# PiWing.net
KiCad netlist of a schematic drawn in EAGLE
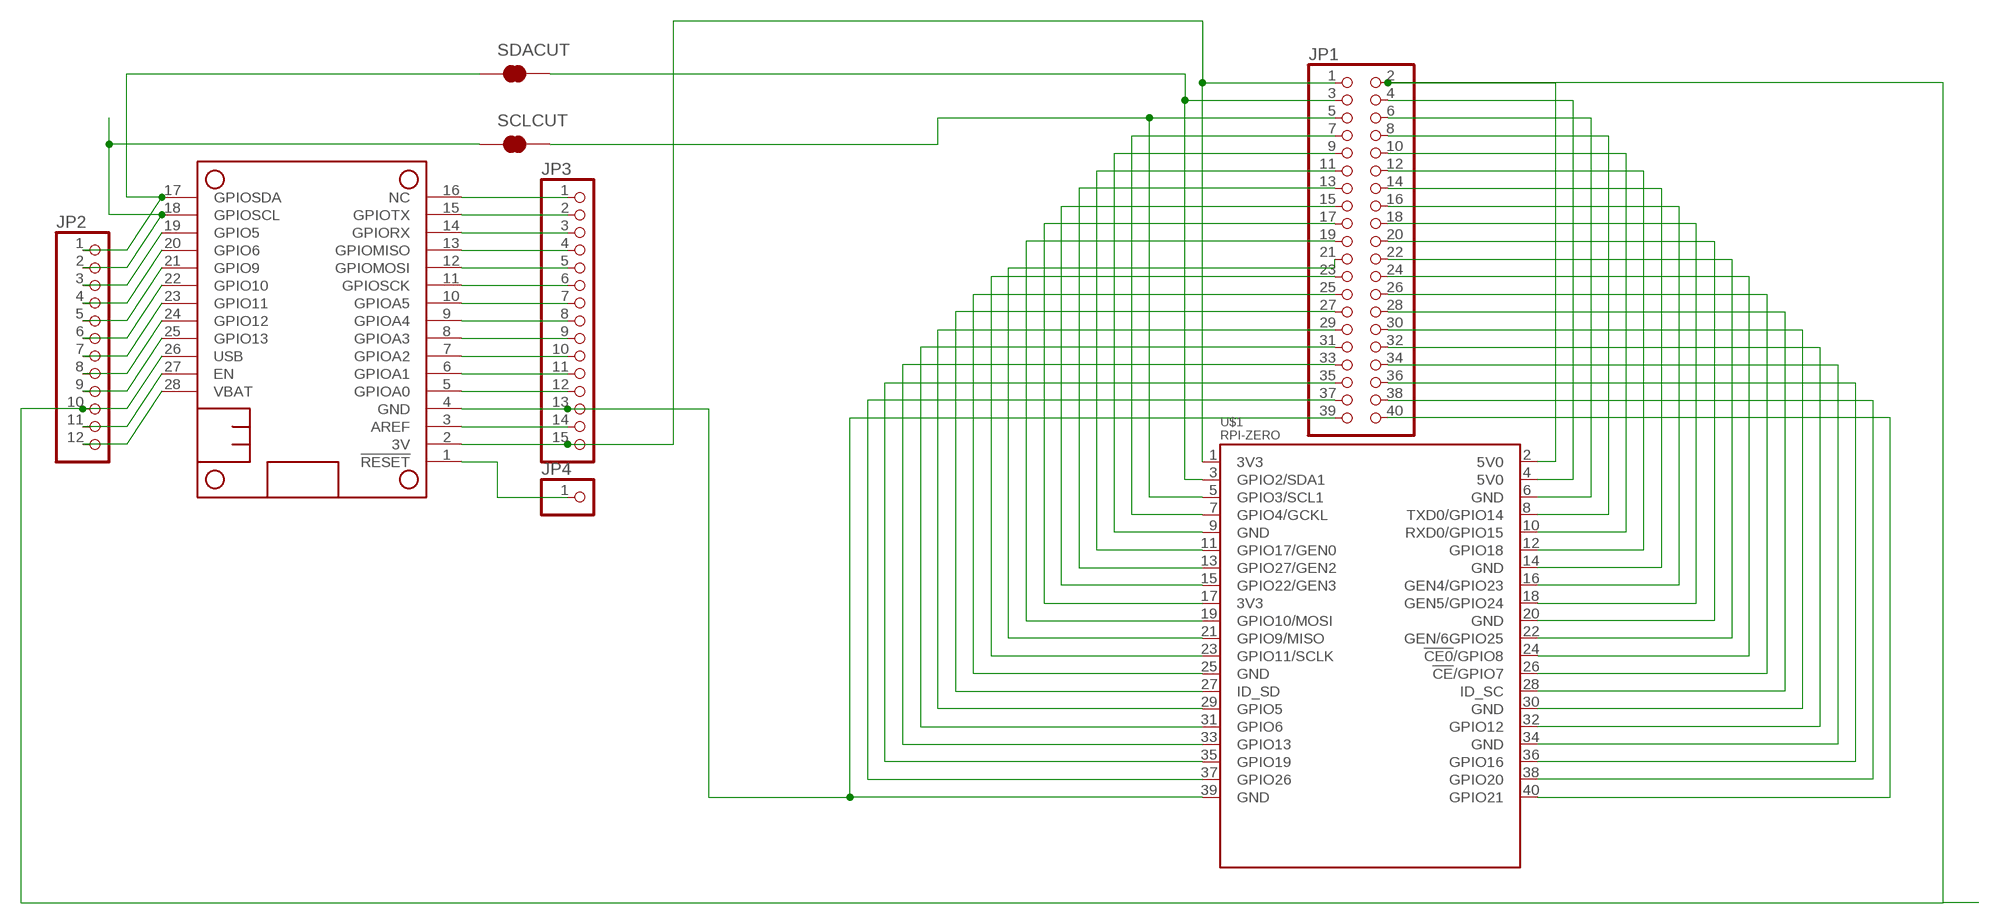
[diagram p0: schematic, sheet 1]

(export (version "E")
  (design (tool "Eeschema 10.0.6"))
  (components
    (comp (ref "JP1")
      (value "PINHD-2X20-BIG")
      (footprint "eagle-import:2X20-BIG")
      (libsource (lib "eagle-import") (part "PINHD-2X20-BIG"))
    )
    (comp (ref "JP2")
      (value "PINHD-1X12-CB")
      (footprint "eagle-import:1X12-CB")
      (libsource (lib "eagle-import") (part "PINHD-1X12-CB"))
    )
    (comp (ref "JP3")
      (value "PINHD-1X15-CB")
      (footprint "eagle-import:1X15-CB")
      (libsource (lib "eagle-import") (part "PINHD-1X15-CB"))
    )
    (comp (ref "JP4")
      (value "PINHD-1X1CB")
      (footprint "eagle-import:1X01-CLEANBIG")
      (libsource (lib "eagle-import") (part "PINHD-1X1CB"))
    )
    (comp (ref "MS1")
      (value "FEATHERWING_NODIM")
      (footprint "eagle-import:FEATHERWING_DIM")
      (libsource (lib "eagle-import") (part "FEATHERWING_NODIM"))
    )
    (comp (ref "SCLCUT")
      (value "JUMPER-SMT_2_NC_TRACE_SILK")
      (footprint "eagle-import:SMT-JUMPER_2_NC_TRACE_SILK")
      (libsource (lib "eagle-import") (part "JUMPER-SMT_2_NC_TRACE_SILK"))
    )
    (comp (ref "SDACUT")
      (value "JUMPER-SMT_2_NC_TRACE_SILK")
      (footprint "eagle-import:SMT-JUMPER_2_NC_TRACE_SILK")
      (libsource (lib "eagle-import") (part "JUMPER-SMT_2_NC_TRACE_SILK"))
    )
    (comp (ref "U$1")
      (value "RPI-ZERO")
      (footprint "eagle-import:RASPBERRYPI_BASTELSTUBE_V13_RASPI_BOARD_B+_FULL")
      (libsource (lib "eagle-import") (part "RPI-ZERO"))
    )
  )
  (nets
    (net (code "1") (name "Net-(JP1-Pad4)") (class "Default")
      (node (ref "JP1") (pin "4") (pinfunction "4_4") (pintype "passive"))
      (node (ref "U$1") (pin "4") (pinfunction "5V0_4") (pintype "power_in"))
    )
    (net (code "2") (name "Net-(JP1-Pad6)") (class "Default")
      (node (ref "JP1") (pin "6") (pinfunction "6_6") (pintype "passive"))
      (node (ref "U$1") (pin "6") (pinfunction "GND_6") (pintype "power_in"))
    )
    (net (code "3") (name "Net-(JP1-Pad9)") (class "Default")
      (node (ref "JP1") (pin "9") (pinfunction "9_9") (pintype "passive"))
      (node (ref "U$1") (pin "9") (pinfunction "GND_9") (pintype "power_in"))
    )
    (net (code "4") (name "Net-(JP1-Pad14)") (class "Default")
      (node (ref "JP1") (pin "14") (pinfunction "14_14") (pintype "passive"))
      (node (ref "U$1") (pin "14") (pinfunction "GND_14") (pintype "power_in"))
    )
    (net (code "5") (name "Net-(JP1-Pad17)") (class "Default")
      (node (ref "JP1") (pin "17") (pinfunction "17_17") (pintype "passive"))
      (node (ref "U$1") (pin "17") (pinfunction "3V3_17") (pintype "power_in"))
    )
    (net (code "6") (name "Net-(JP1-Pad20)") (class "Default")
      (node (ref "JP1") (pin "20") (pinfunction "20_20") (pintype "passive"))
      (node (ref "U$1") (pin "20") (pinfunction "GND_20") (pintype "power_in"))
    )
    (net (code "7") (name "Net-(JP1-Pad25)") (class "Default")
      (node (ref "JP1") (pin "25") (pinfunction "25_25") (pintype "passive"))
      (node (ref "U$1") (pin "25") (pinfunction "GND_25") (pintype "power_in"))
    )
    (net (code "8") (name "Net-(JP1-Pad30)") (class "Default")
      (node (ref "JP1") (pin "30") (pinfunction "30_30") (pintype "passive"))
      (node (ref "U$1") (pin "30") (pinfunction "GND_30") (pintype "power_in"))
    )
    (net (code "9") (name "Net-(JP1-Pad34)") (class "Default")
      (node (ref "JP1") (pin "34") (pinfunction "34_34") (pintype "passive"))
      (node (ref "U$1") (pin "34") (pinfunction "GND_34") (pintype "power_in"))
    )
    (net (code "10") (name "Net-(MS1-3V)") (class "Default")
      (node (ref "JP1") (pin "1") (pinfunction "1_1") (pintype "passive"))
      (node (ref "JP3") (pin "15") (pinfunction "15_15") (pintype "passive"))
      (node (ref "MS1") (pin "2") (pinfunction "3V_2") (pintype "power_in"))
      (node (ref "U$1") (pin "1") (pinfunction "3V3_1") (pintype "power_in"))
    )
    (net (code "11") (name "Net-(MS1-AREF)") (class "Default")
      (node (ref "JP3") (pin "14") (pinfunction "14_14") (pintype "passive"))
      (node (ref "MS1") (pin "3") (pinfunction "AREF_3") (pintype "passive"))
    )
    (net (code "12") (name "Net-(MS1-EN)") (class "Default")
      (node (ref "JP2") (pin "11") (pinfunction "11_11") (pintype "passive"))
      (node (ref "MS1") (pin "27") (pinfunction "EN_27") (pintype "passive"))
    )
    (net (code "13") (name "Net-(MS1-GND)") (class "Default")
      (node (ref "JP1") (pin "39") (pinfunction "39_39") (pintype "passive"))
      (node (ref "JP3") (pin "13") (pinfunction "13_13") (pintype "passive"))
      (node (ref "MS1") (pin "4") (pinfunction "GND_4") (pintype "power_in"))
      (node (ref "U$1") (pin "39") (pinfunction "GND_39") (pintype "power_in"))
    )
    (net (code "14") (name "Net-(MS1-GPIO5)") (class "Default")
      (node (ref "JP2") (pin "3") (pinfunction "3_3") (pintype "passive"))
      (node (ref "MS1") (pin "19") (pinfunction "GPIO5_19") (pintype "bidirectional"))
    )
    (net (code "15") (name "Net-(MS1-GPIO6)") (class "Default")
      (node (ref "JP2") (pin "4") (pinfunction "4_4") (pintype "passive"))
      (node (ref "MS1") (pin "20") (pinfunction "GPIO6_20") (pintype "bidirectional"))
    )
    (net (code "16") (name "Net-(MS1-GPIO9)") (class "Default")
      (node (ref "JP2") (pin "5") (pinfunction "5_5") (pintype "passive"))
      (node (ref "MS1") (pin "21") (pinfunction "GPIO9_21") (pintype "bidirectional"))
    )
    (net (code "17") (name "Net-(MS1-GPIO10)") (class "Default")
      (node (ref "JP2") (pin "6") (pinfunction "6_6") (pintype "passive"))
      (node (ref "MS1") (pin "22") (pinfunction "GPIO10_22") (pintype "bidirectional"))
    )
    (net (code "18") (name "Net-(MS1-GPIO11)") (class "Default")
      (node (ref "JP2") (pin "7") (pinfunction "7_7") (pintype "passive"))
      (node (ref "MS1") (pin "23") (pinfunction "GPIO11_23") (pintype "bidirectional"))
    )
    (net (code "19") (name "Net-(MS1-GPIO12)") (class "Default")
      (node (ref "JP2") (pin "8") (pinfunction "8_8") (pintype "passive"))
      (node (ref "MS1") (pin "24") (pinfunction "GPIO12_24") (pintype "bidirectional"))
    )
    (net (code "20") (name "Net-(MS1-GPIO13)") (class "Default")
      (node (ref "JP2") (pin "9") (pinfunction "9_9") (pintype "passive"))
      (node (ref "MS1") (pin "25") (pinfunction "GPIO13_25") (pintype "bidirectional"))
    )
    (net (code "21") (name "Net-(MS1-GPIOA0)") (class "Default")
      (node (ref "JP3") (pin "12") (pinfunction "12_12") (pintype "passive"))
      (node (ref "MS1") (pin "5") (pinfunction "GPIOA0_5") (pintype "bidirectional"))
    )
    (net (code "22") (name "Net-(MS1-GPIOA1)") (class "Default")
      (node (ref "JP3") (pin "11") (pinfunction "11_11") (pintype "passive"))
      (node (ref "MS1") (pin "6") (pinfunction "GPIOA1_6") (pintype "bidirectional"))
    )
    (net (code "23") (name "Net-(MS1-GPIOA2)") (class "Default")
      (node (ref "JP3") (pin "10") (pinfunction "10_10") (pintype "passive"))
      (node (ref "MS1") (pin "7") (pinfunction "GPIOA2_7") (pintype "bidirectional"))
    )
    (net (code "24") (name "Net-(MS1-GPIOA3)") (class "Default")
      (node (ref "JP3") (pin "9") (pinfunction "9_9") (pintype "passive"))
      (node (ref "MS1") (pin "8") (pinfunction "GPIOA3_8") (pintype "bidirectional"))
    )
    (net (code "25") (name "Net-(MS1-GPIOA4)") (class "Default")
      (node (ref "JP3") (pin "8") (pinfunction "8_8") (pintype "passive"))
      (node (ref "MS1") (pin "9") (pinfunction "GPIOA4_9") (pintype "bidirectional"))
    )
    (net (code "26") (name "Net-(MS1-GPIOA5)") (class "Default")
      (node (ref "JP3") (pin "7") (pinfunction "7_7") (pintype "passive"))
      (node (ref "MS1") (pin "10") (pinfunction "GPIOA5_10") (pintype "bidirectional"))
    )
    (net (code "27") (name "Net-(MS1-GPIOMISO)") (class "Default")
      (node (ref "JP3") (pin "4") (pinfunction "4_4") (pintype "passive"))
      (node (ref "MS1") (pin "13") (pinfunction "GPIOMISO_13") (pintype "bidirectional"))
    )
    (net (code "28") (name "Net-(MS1-GPIOMOSI)") (class "Default")
      (node (ref "JP3") (pin "5") (pinfunction "5_5") (pintype "passive"))
      (node (ref "MS1") (pin "12") (pinfunction "GPIOMOSI_12") (pintype "bidirectional"))
    )
    (net (code "29") (name "Net-(MS1-GPIORX)") (class "Default")
      (node (ref "JP3") (pin "3") (pinfunction "3_3") (pintype "passive"))
      (node (ref "MS1") (pin "14") (pinfunction "GPIORX_14") (pintype "bidirectional"))
    )
    (net (code "30") (name "Net-(MS1-GPIOSCK)") (class "Default")
      (node (ref "JP3") (pin "6") (pinfunction "6_6") (pintype "passive"))
      (node (ref "MS1") (pin "11") (pinfunction "GPIOSCK_11") (pintype "bidirectional"))
    )
    (net (code "31") (name "Net-(MS1-GPIOSCL)") (class "Default")
      (node (ref "JP2") (pin "2") (pinfunction "2_2") (pintype "passive"))
      (node (ref "MS1") (pin "18") (pinfunction "GPIOSCL_18") (pintype "bidirectional"))
      (node (ref "SCLCUT") (pin "1") (pinfunction "1_1") (pintype "passive"))
    )
    (net (code "32") (name "Net-(MS1-GPIOSDA)") (class "Default")
      (node (ref "JP2") (pin "1") (pinfunction "1_1") (pintype "passive"))
      (node (ref "MS1") (pin "17") (pinfunction "GPIOSDA_17") (pintype "bidirectional"))
      (node (ref "SDACUT") (pin "1") (pinfunction "1_1") (pintype "passive"))
    )
    (net (code "33") (name "Net-(MS1-GPIOTX)") (class "Default")
      (node (ref "JP3") (pin "2") (pinfunction "2_2") (pintype "passive"))
      (node (ref "MS1") (pin "15") (pinfunction "GPIOTX_15") (pintype "bidirectional"))
    )
    (net (code "34") (name "Net-(MS1-NC)") (class "Default")
      (node (ref "JP3") (pin "1") (pinfunction "1_1") (pintype "passive"))
      (node (ref "MS1") (pin "16") (pinfunction "NC_16") (pintype "passive"))
    )
    (net (code "35") (name "Net-(MS1-USB)") (class "Default")
      (node (ref "JP1") (pin "2") (pinfunction "2_2") (pintype "passive"))
      (node (ref "JP2") (pin "10") (pinfunction "10_10") (pintype "passive"))
      (node (ref "MS1") (pin "26") (pinfunction "USB_26") (pintype "power_in"))
      (node (ref "U$1") (pin "2") (pinfunction "5V0_2") (pintype "power_in"))
    )
    (net (code "36") (name "Net-(MS1-VBAT)") (class "Default")
      (node (ref "JP2") (pin "12") (pinfunction "12_12") (pintype "passive"))
      (node (ref "MS1") (pin "28") (pinfunction "VBAT_28") (pintype "power_in"))
    )
    (net (code "37") (name "Net-(MS1-~{RESET})") (class "Default")
      (node (ref "JP4") (pin "1") (pinfunction "1_1") (pintype "passive"))
      (node (ref "MS1") (pin "1") (pinfunction "~{RESET}_1") (pintype "input"))
    )
    (net (code "38") (name "Net-(U$1-GEN4{slash}GPIO23)") (class "Default")
      (node (ref "JP1") (pin "16") (pinfunction "16_16") (pintype "passive"))
      (node (ref "U$1") (pin "16") (pinfunction "GEN4/GPIO23_16") (pintype "bidirectional"))
    )
    (net (code "39") (name "Net-(U$1-GEN5{slash}GPIO24)") (class "Default")
      (node (ref "JP1") (pin "18") (pinfunction "18_18") (pintype "passive"))
      (node (ref "U$1") (pin "18") (pinfunction "GEN5/GPIO24_18") (pintype "bidirectional"))
    )
    (net (code "40") (name "Net-(U$1-GEN{slash}6GPIO25)") (class "Default")
      (node (ref "JP1") (pin "22") (pinfunction "22_22") (pintype "passive"))
      (node (ref "U$1") (pin "22") (pinfunction "GEN/6GPIO25_22") (pintype "bidirectional"))
    )
    (net (code "41") (name "Net-(U$1-GPIO2{slash}SDA1)") (class "Default")
      (node (ref "JP1") (pin "3") (pinfunction "3_3") (pintype "passive"))
      (node (ref "SDACUT") (pin "2") (pinfunction "2_2") (pintype "passive"))
      (node (ref "U$1") (pin "3") (pinfunction "GPIO2/SDA1_3") (pintype "bidirectional"))
    )
    (net (code "42") (name "Net-(U$1-GPIO3{slash}SCL1)") (class "Default")
      (node (ref "JP1") (pin "5") (pinfunction "5_5") (pintype "passive"))
      (node (ref "SCLCUT") (pin "2") (pinfunction "2_2") (pintype "passive"))
      (node (ref "U$1") (pin "5") (pinfunction "GPIO3/SCL1_5") (pintype "bidirectional"))
    )
    (net (code "43") (name "Net-(U$1-GPIO4{slash}GCKL)") (class "Default")
      (node (ref "JP1") (pin "7") (pinfunction "7_7") (pintype "passive"))
      (node (ref "U$1") (pin "7") (pinfunction "GPIO4/GCKL_7") (pintype "bidirectional"))
    )
    (net (code "44") (name "Net-(U$1-GPIO5)") (class "Default")
      (node (ref "JP1") (pin "29") (pinfunction "29_29") (pintype "passive"))
      (node (ref "U$1") (pin "29") (pinfunction "GPIO5_29") (pintype "bidirectional"))
    )
    (net (code "45") (name "Net-(U$1-GPIO6)") (class "Default")
      (node (ref "JP1") (pin "31") (pinfunction "31_31") (pintype "passive"))
      (node (ref "U$1") (pin "31") (pinfunction "GPIO6_31") (pintype "bidirectional"))
    )
    (net (code "46") (name "Net-(U$1-GPIO9{slash}MISO)") (class "Default")
      (node (ref "JP1") (pin "21") (pinfunction "21_21") (pintype "passive"))
      (node (ref "U$1") (pin "21") (pinfunction "GPIO9/MISO_21") (pintype "bidirectional"))
    )
    (net (code "47") (name "Net-(U$1-GPIO10{slash}MOSI)") (class "Default")
      (node (ref "JP1") (pin "19") (pinfunction "19_19") (pintype "passive"))
      (node (ref "U$1") (pin "19") (pinfunction "GPIO10/MOSI_19") (pintype "bidirectional"))
    )
    (net (code "48") (name "Net-(U$1-GPIO11{slash}SCLK)") (class "Default")
      (node (ref "JP1") (pin "23") (pinfunction "23_23") (pintype "passive"))
      (node (ref "U$1") (pin "23") (pinfunction "GPIO11/SCLK_23") (pintype "bidirectional"))
    )
    (net (code "49") (name "Net-(U$1-GPIO12)") (class "Default")
      (node (ref "JP1") (pin "32") (pinfunction "32_32") (pintype "passive"))
      (node (ref "U$1") (pin "32") (pinfunction "GPIO12_32") (pintype "bidirectional"))
    )
    (net (code "50") (name "Net-(U$1-GPIO13)") (class "Default")
      (node (ref "JP1") (pin "33") (pinfunction "33_33") (pintype "passive"))
      (node (ref "U$1") (pin "33") (pinfunction "GPIO13_33") (pintype "bidirectional"))
    )
    (net (code "51") (name "Net-(U$1-GPIO16)") (class "Default")
      (node (ref "JP1") (pin "36") (pinfunction "36_36") (pintype "passive"))
      (node (ref "U$1") (pin "36") (pinfunction "GPIO16_36") (pintype "bidirectional"))
    )
    (net (code "52") (name "Net-(U$1-GPIO17{slash}GEN0)") (class "Default")
      (node (ref "JP1") (pin "11") (pinfunction "11_11") (pintype "passive"))
      (node (ref "U$1") (pin "11") (pinfunction "GPIO17/GEN0_11") (pintype "bidirectional"))
    )
    (net (code "53") (name "Net-(U$1-GPIO18)") (class "Default")
      (node (ref "JP1") (pin "12") (pinfunction "12_12") (pintype "passive"))
      (node (ref "U$1") (pin "12") (pinfunction "GPIO18_12") (pintype "bidirectional"))
    )
    (net (code "54") (name "Net-(U$1-GPIO19)") (class "Default")
      (node (ref "JP1") (pin "35") (pinfunction "35_35") (pintype "passive"))
      (node (ref "U$1") (pin "35") (pinfunction "GPIO19_35") (pintype "bidirectional"))
    )
    (net (code "55") (name "Net-(U$1-GPIO20)") (class "Default")
      (node (ref "JP1") (pin "38") (pinfunction "38_38") (pintype "passive"))
      (node (ref "U$1") (pin "38") (pinfunction "GPIO20_38") (pintype "bidirectional"))
    )
    (net (code "56") (name "Net-(U$1-GPIO21)") (class "Default")
      (node (ref "JP1") (pin "40") (pinfunction "40_40") (pintype "passive"))
      (node (ref "U$1") (pin "40") (pinfunction "GPIO21_40") (pintype "bidirectional"))
    )
    (net (code "57") (name "Net-(U$1-GPIO22{slash}GEN3)") (class "Default")
      (node (ref "JP1") (pin "15") (pinfunction "15_15") (pintype "passive"))
      (node (ref "U$1") (pin "15") (pinfunction "GPIO22/GEN3_15") (pintype "bidirectional"))
    )
    (net (code "58") (name "Net-(U$1-GPIO26)") (class "Default")
      (node (ref "JP1") (pin "37") (pinfunction "37_37") (pintype "passive"))
      (node (ref "U$1") (pin "37") (pinfunction "GPIO26_37") (pintype "bidirectional"))
    )
    (net (code "59") (name "Net-(U$1-GPIO27{slash}GEN2)") (class "Default")
      (node (ref "JP1") (pin "13") (pinfunction "13_13") (pintype "passive"))
      (node (ref "U$1") (pin "13") (pinfunction "GPIO27/GEN2_13") (pintype "bidirectional"))
    )
    (net (code "60") (name "Net-(U$1-ID_SC)") (class "Default")
      (node (ref "JP1") (pin "28") (pinfunction "28_28") (pintype "passive"))
      (node (ref "U$1") (pin "28") (pinfunction "ID_SC_28") (pintype "bidirectional"))
    )
    (net (code "61") (name "Net-(U$1-ID_SD)") (class "Default")
      (node (ref "JP1") (pin "27") (pinfunction "27_27") (pintype "passive"))
      (node (ref "U$1") (pin "27") (pinfunction "ID_SD_27") (pintype "bidirectional"))
    )
    (net (code "62") (name "Net-(U$1-RXD0{slash}GPIO15)") (class "Default")
      (node (ref "JP1") (pin "10") (pinfunction "10_10") (pintype "passive"))
      (node (ref "U$1") (pin "10") (pinfunction "RXD0/GPIO15_10") (pintype "bidirectional"))
    )
    (net (code "63") (name "Net-(U$1-TXD0{slash}GPIO14)") (class "Default")
      (node (ref "JP1") (pin "8") (pinfunction "8_8") (pintype "passive"))
      (node (ref "U$1") (pin "8") (pinfunction "TXD0/GPIO14_8") (pintype "bidirectional"))
    )
    (net (code "64") (name "Net-(U$1-~{CE0}{slash}GPIO8)") (class "Default")
      (node (ref "JP1") (pin "24") (pinfunction "24_24") (pintype "passive"))
      (node (ref "U$1") (pin "24") (pinfunction "~{CE0}/GPIO8_24") (pintype "bidirectional"))
    )
    (net (code "65") (name "Net-(U$1-~{CE}{slash}GPIO7)") (class "Default")
      (node (ref "JP1") (pin "26") (pinfunction "26_26") (pintype "passive"))
      (node (ref "U$1") (pin "26") (pinfunction "~{CE}/GPIO7_26") (pintype "bidirectional"))
    )
  )
)
